# mcu_core.net
KiCad netlist of a schematic drawn in Altium Designer
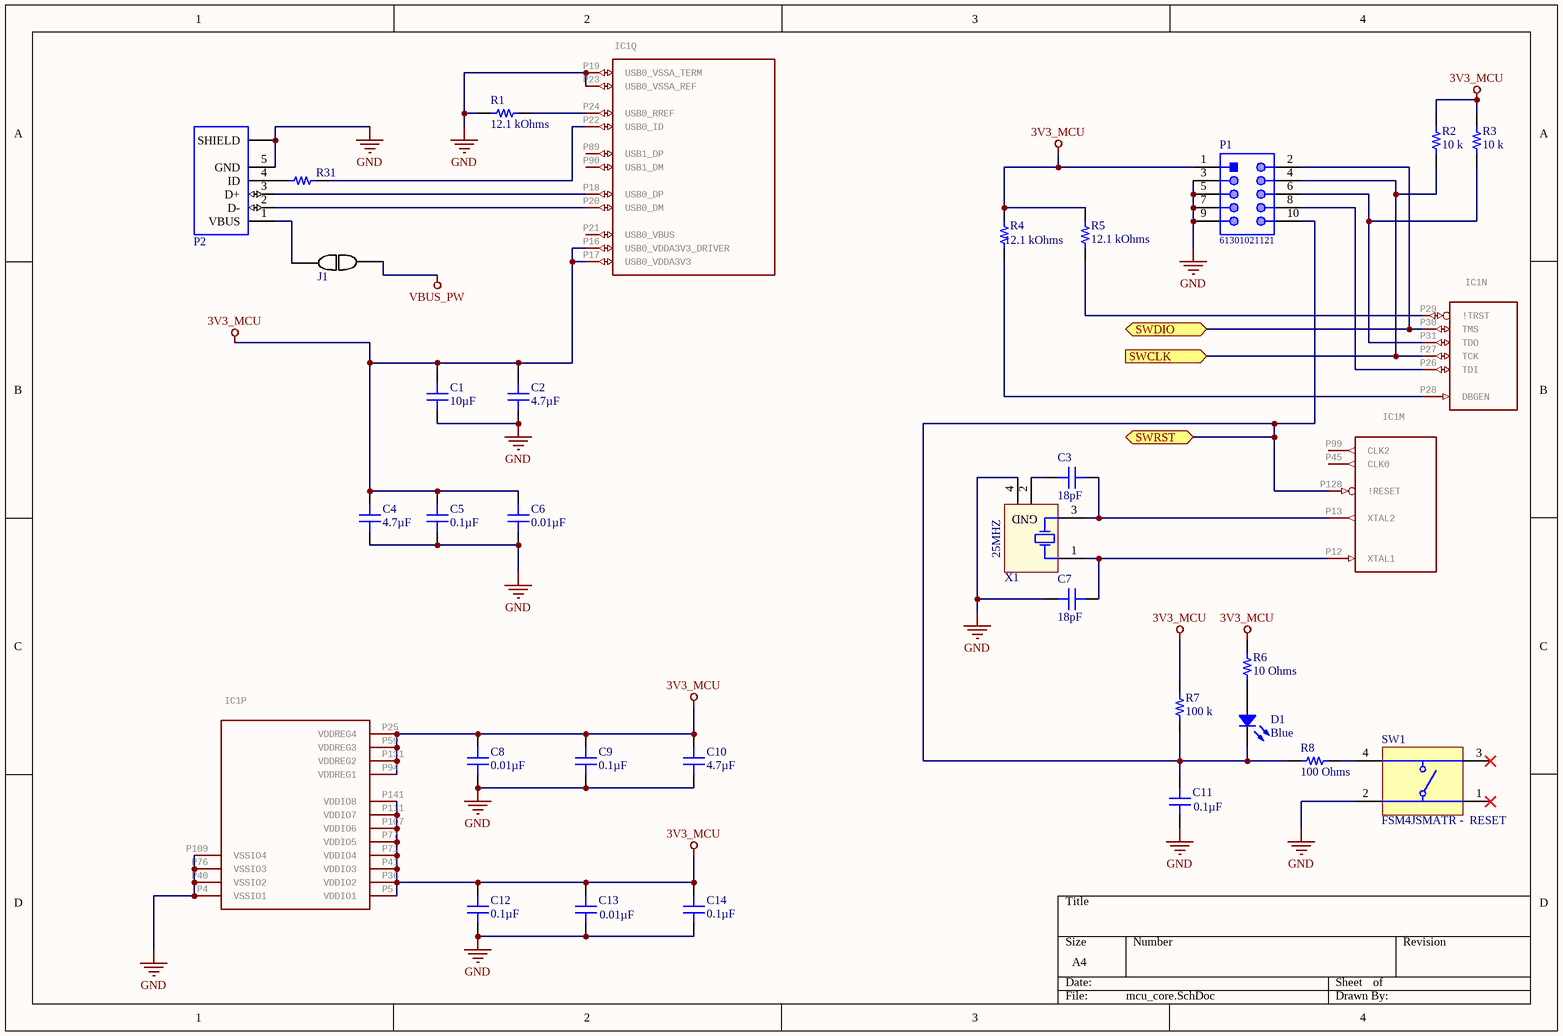
[diagram p0: mcu_core.SchDoc]

(export (version "E")
  (design (tool "Eeschema 10.0.6"))
  (components
    (comp (ref "C1")
      (value "10µF")
      (footprint "CAP 0603_1608")
      (description "CAP CER 10UF 10V X5R 0603")
      (fields
        (field (name "PART NUMBER") "GRM188R61A106MAALD")
        (field (name "MANUFACTURER") "Murata Electronics")
      )
      (libsource (lib "Celestial Altium Library - altium_library (2)") (part "Capacitor"))
    )
    (comp (ref "C2")
      (value "4.7µF")
      (footprint "CAP 0603_1608")
      (description "CAP CER 4.7UF 10V X5R 0603")
      (fields (field (name "PART NUMBER") "LMK107BJ475KA-T") (field (name "MANUFACTURER") "Taiyo Yuden"))
      (libsource (lib "Celestial Altium Library - altium_library (2)") (part "Capacitor"))
    )
    (comp (ref "C3")
      (value "18pF")
      (footprint "CAP 0603_1608")
      (description "CAP CER 18PF 10V C0G/NP0 0603")
      (fields
        (field (name "PART NUMBER") "VJ0603A180FXQCW1BC")
        (field (name "MANUFACTURER") "Vishay Vitramon")
      )
      (libsource (lib "Celestial Altium Library - altium_library (2)") (part "Capacitor"))
    )
    (comp (ref "C4")
      (value "4.7µF")
      (footprint "CAP 0603_1608")
      (description "CAP CER 4.7UF 10V X5R 0603")
      (fields (field (name "PART NUMBER") "LMK107BJ475KA-T") (field (name "MANUFACTURER") "Taiyo Yuden"))
      (libsource (lib "Celestial Altium Library - altium_library (2)") (part "Capacitor"))
    )
    (comp (ref "C5")
      (value "0.1µF")
      (footprint "CAP 0603_1608")
      (description "CAP CER 0.1UF 50V X7R 0603")
      (fields (field (name "PART NUMBER") "C0603C104K5RAC7411") (field (name "MANUFACTURER") "KEMET"))
      (libsource (lib "Celestial Altium Library - altium_library (2)") (part "Capacitor"))
    )
    (comp (ref "C6")
      (value "0.01µF")
      (footprint "CAP 0603_1608")
      (description "CAP CER 0.01UF 250V X7R 0603")
      (fields (field (name "PART NUMBER") "C0603C103KARACAUTO") (field (name "MANUFACTURER") "KEMET"))
      (libsource (lib "Celestial Altium Library - altium_library (2)") (part "Capacitor"))
    )
    (comp (ref "C7")
      (value "18pF")
      (footprint "CAP 0603_1608")
      (description "CAP CER 18PF 10V C0G/NP0 0603")
      (fields
        (field (name "PART NUMBER") "VJ0603A180FXQCW1BC")
        (field (name "MANUFACTURER") "Vishay Vitramon")
      )
      (libsource (lib "Celestial Altium Library - altium_library (2)") (part "Capacitor"))
    )
    (comp (ref "C8")
      (value "0.01µF")
      (footprint "CAP 0603_1608")
      (description "CAP CER 0.01UF 250V X7R 0603")
      (fields (field (name "PART NUMBER") "C0603C103KARACAUTO") (field (name "MANUFACTURER") "KEMET"))
      (libsource (lib "Celestial Altium Library - altium_library (2)") (part "Capacitor"))
    )
    (comp (ref "C9")
      (value "0.1µF")
      (footprint "CAP 0603_1608")
      (description "CAP CER 0.1UF 50V X7R 0603")
      (fields (field (name "PART NUMBER") "C0603C104K5RAC7411") (field (name "MANUFACTURER") "KEMET"))
      (libsource (lib "Celestial Altium Library - altium_library (2)") (part "Capacitor"))
    )
    (comp (ref "C10")
      (value "4.7µF")
      (footprint "CAP 0603_1608")
      (description "CAP CER 4.7UF 10V X5R 0603")
      (fields (field (name "PART NUMBER") "LMK107BJ475KA-T") (field (name "MANUFACTURER") "Taiyo Yuden"))
      (libsource (lib "Celestial Altium Library - altium_library (2)") (part "Capacitor"))
    )
    (comp (ref "C11")
      (value "0.1µF")
      (footprint "CAP 0603_1608")
      (description "CAP CER 0.1UF 10V X7R 0603")
      (fields (field (name "PART NUMBER") "C0603T104K8RAC7867") (field (name "MANUFACTURER") "KEMET"))
      (libsource (lib "Celestial Altium Library - altium_library (2)") (part "Capacitor"))
    )
    (comp (ref "C12")
      (value "0.1µF")
      (footprint "CAP 0603_1608")
      (description "CAP CER 0.1UF 50V X7R 0603")
      (fields (field (name "PART NUMBER") "C0603C104K5RAC7411") (field (name "MANUFACTURER") "KEMET"))
      (libsource (lib "Celestial Altium Library - altium_library (2)") (part "Capacitor"))
    )
    (comp (ref "C13")
      (value "0.01µF")
      (footprint "CAP 0603_1608")
      (description "CAP CER 0.01UF 250V X7R 0603")
      (fields (field (name "PART NUMBER") "C0603C103KARACAUTO") (field (name "MANUFACTURER") "KEMET"))
      (libsource (lib "Celestial Altium Library - altium_library (2)") (part "Capacitor"))
    )
    (comp (ref "C14")
      (value "0.1µF")
      (footprint "CAP 0603_1608")
      (description "CAP CER 0.1UF 50V X7R 0603")
      (fields (field (name "PART NUMBER") "C0603C104K5RAC7411") (field (name "MANUFACTURER") "KEMET"))
      (libsource (lib "Celestial Altium Library - altium_library (2)") (part "Capacitor"))
    )
    (comp (ref "D1")
      (value "Blue")
      (footprint "LED 0603_1608 BLUE")
      (description "LED BLUE 0603 SMD")
      (fields
        (field (name "PART NUMBER") "VLMB1300-GS08")
        (field (name "MANUFACTURER") "Vishay Semiconductor Opto Division")
      )
      (libsource (lib "Celestial Altium Library - altium_library (2)") (part "LED"))
    )
    (comp (ref "IC1")
      (value "LQFP144 - SOT486-1    LQFP144: plastic low profile quad flat package; 144 leads; body 20 x 20 x 1.4 mm    body + leads 22 x 22 mm   Solderland (pads) 0.4 x 1.5 mm on corners (8 x) and 0.28 x 1.5 mm (136 x)")
      (footprint "LQFP144")
      (libsource (lib "LPC4300") (part "LPC4300_LQFP144"))
    )
    (comp (ref "J1")
      (value "103185-2")
      (footprint "TE_103185-2")
      (description "02 MODII HDR SRST B/A .100CL")
      (libsource (lib "103185-2") (part "103185-2"))
    )
    (comp (ref "P1")
      (value "61301021121")
      (footprint "61301021121")
      (description "THT Vertical Pin Header WR-PHD, Pitch 2.54 mm, Dual Row, 10 pins")
      (fields (field (name "MANUFACTURER") "Wurth Elektronik") (field (name "PUBLISHER") "WurthElektronik"))
      (libsource (lib "Altium Content Vault") (part "WE-CN-2P-M-R10"))
    )
    (comp (ref "P2")
      (value "47346-0001")
      (footprint "MOLEX_47346-0001")
      (description "CONN RCPT 5POS MICRO USB R/A  SMD")
      (libsource (lib "47346-0001") (part "47346-0001"))
    )
    (comp (ref "R1")
      (value "12.1 kOhms")
      (footprint "RES 0603_1608")
      (description "RES SMD 12.1K OHM 1% 1/10W 0603")
      (fields (field (name "PART NUMBER") "CR0603-FX-1212ELF") (field (name "MANUFACTURER") "Bourns Inc."))
      (libsource (lib "Celestial Altium Library - altium_library (2)") (part "Resistor"))
    )
    (comp (ref "R2")
      (value "10 k")
      (footprint "RES 0603_1608")
      (description "RES 10K OHM 0.1% 1/16W 0603")
      (fields
        (field (name "PART NUMBER") "RNCS0603BKE10K0")
        (field (name "MANUFACTURER") "Stackpole Electronics Inc")
      )
      (libsource (lib "Celestial Altium Library - altium_library (2)") (part "Resistor"))
    )
    (comp (ref "R3")
      (value "10 k")
      (footprint "RES 0603_1608")
      (description "RES 10K OHM 0.1% 1/16W 0603")
      (fields
        (field (name "PART NUMBER") "RNCS0603BKE10K0")
        (field (name "MANUFACTURER") "Stackpole Electronics Inc")
      )
      (libsource (lib "Celestial Altium Library - altium_library (2)") (part "Resistor"))
    )
    (comp (ref "R4")
      (value "12.1 kOhms")
      (footprint "RES 0603_1608")
      (description "RES SMD 12.1K OHM 1% 1/10W 0603")
      (fields (field (name "PART NUMBER") "CR0603-FX-1212ELF") (field (name "MANUFACTURER") "Bourns Inc."))
      (libsource (lib "Celestial Altium Library - altium_library (2)") (part "Resistor"))
    )
    (comp (ref "R5")
      (value "12.1 kOhms")
      (footprint "RES 0603_1608")
      (description "RES SMD 12.1K OHM 1% 1/10W 0603")
      (fields (field (name "PART NUMBER") "CR0603-FX-1212ELF") (field (name "MANUFACTURER") "Bourns Inc."))
      (libsource (lib "Celestial Altium Library - altium_library (2)") (part "Resistor"))
    )
    (comp (ref "R6")
      (value "10 Ohms")
      (footprint "RES 0603_1608")
      (description "RES SMD 10 OHM 0.1% 1/10W 0603")
      (fields (field (name "PART NUMBER") "CRT0603-BY-10R0ELF") (field (name "MANUFACTURER") "Bourns Inc."))
      (libsource (lib "Celestial Altium Library - altium_library (2)") (part "Resistor"))
    )
    (comp (ref "R7")
      (value "100 k")
      (footprint "RES 0603_1608")
      (description "RES 100K OHM 5% 1/10W 0603")
      (fields
        (field (name "PART NUMBER") "RMCF0603JT100K")
        (field (name "MANUFACTURER") "Stackpole Electronics Inc")
      )
      (libsource (lib "Celestial Altium Library - altium_library (2)") (part "Resistor"))
    )
    (comp (ref "R8")
      (value "100 Ohms")
      (footprint "RES 0603_1608")
      (description "RES 100 OHM 0.1% 1/16W 0603")
      (fields
        (field (name "PART NUMBER") "RNCS0603BKE100R")
        (field (name "MANUFACTURER") "Stackpole Electronics Inc")
      )
      (libsource (lib "Celestial Altium Library - altium_library (2)") (part "Resistor"))
    )
    (comp (ref "R31")
      (value "~")
      (footprint "RES 0603_1608")
      (description "RES 0 OHM JUMPER 0603")
      (fields
        (field (name "PART NUMBER") "TLRZ1JTTD")
        (field (name "MANUFACTURER") "KOA Speer Electronics, Inc.")
      )
      (libsource (lib "Celestial Altium Library - altium_library (2)") (part "Resistor"))
    )
    (comp (ref "SW1")
      (value "FSM4JSMATR -  RESET")
      (footprint "TECO-FSM4JSMATR_V")
      (description "Micro Miniature Push Button Switch FSM JSM, 50 mA, -35 to 85 degC, 4-Pin SMD, RoHS, Tape and Reel")
      (fields (field (name "MANUFACTURER") "TE Connectivity"))
      (libsource (lib "Altium Content Vault") (part "SW-SPST-4_A"))
    )
    (comp (ref "X1")
      (value "25MHZ")
      (footprint "ABRA-ABMM2-4_V")
      (fields (field (name "MANUFACTURER") "Abracon") (field (name "PARTNUMBER") "ABMM2-8.000MHZ-E2-T"))
      (libsource (lib "Altium Content Vault") (part "ABRA-XTAL_1-3-4"))
    )
  )
  (nets
    (net (code "1") (name "/SWCLK") (class "Default")
      (node (ref "IC1") (pin "P27") (pinfunction "TCK_P27") (pintype "bidirectional"))
      (node (ref "P1") (pin "4") (pinfunction "4_4") (pintype "passive"))
      (node (ref "R2") (pin "1") (pinfunction "1_1") (pintype "passive"))
    )
    (net (code "2") (name "/SWDIO") (class "Default")
      (node (ref "IC1") (pin "P30") (pinfunction "TMS_P30") (pintype "bidirectional"))
      (node (ref "P1") (pin "2") (pinfunction "2_2") (pintype "passive"))
    )
    (net (code "3") (name "/SWRST") (class "Default")
      (node (ref "C11") (pin "1") (pinfunction "1_1") (pintype "passive"))
      (node (ref "D1") (pin "2") (pinfunction "2_2") (pintype "passive"))
      (node (ref "IC1") (pin "P128") (pinfunction "!RESET_P128") (pintype "input"))
      (node (ref "P1") (pin "10") (pinfunction "10_10") (pintype "passive"))
      (node (ref "R7") (pin "2") (pinfunction "2_2") (pintype "passive"))
      (node (ref "R8") (pin "2") (pinfunction "2_2") (pintype "passive"))
    )
    (net (code "4") (name "3V3_MCU") (class "Default")
      (node (ref "C1") (pin "2") (pinfunction "2_2") (pintype "passive"))
      (node (ref "C10") (pin "2") (pinfunction "2_2") (pintype "passive"))
      (node (ref "C12") (pin "2") (pinfunction "2_2") (pintype "passive"))
      (node (ref "C13") (pin "2") (pinfunction "2_2") (pintype "passive"))
      (node (ref "C14") (pin "2") (pinfunction "2_2") (pintype "passive"))
      (node (ref "C2") (pin "2") (pinfunction "2_2") (pintype "passive"))
      (node (ref "C4") (pin "2") (pinfunction "2_2") (pintype "passive"))
      (node (ref "C5") (pin "2") (pinfunction "2_2") (pintype "passive"))
      (node (ref "C6") (pin "2") (pinfunction "2_2") (pintype "passive"))
      (node (ref "C8") (pin "2") (pinfunction "2_2") (pintype "passive"))
      (node (ref "C9") (pin "2") (pinfunction "2_2") (pintype "passive"))
      (node (ref "IC1") (pin "P107") (pinfunction "VDDIO6_P107") (pintype "power_in"))
      (node (ref "IC1") (pin "P111") (pinfunction "VDDIO7_P111") (pintype "power_in"))
      (node (ref "IC1") (pin "P131") (pinfunction "VDDREG2_P131") (pintype "power_in"))
      (node (ref "IC1") (pin "P141") (pinfunction "VDDIO8_P141") (pintype "power_in"))
      (node (ref "IC1") (pin "P16") (pinfunction "USB0_VDDA3V3_DRIVER_P16") (pintype "bidirectional"))
      (node (ref "IC1") (pin "P17") (pinfunction "USB0_VDDA3V3_P17") (pintype "bidirectional"))
      (node (ref "IC1") (pin "P25") (pinfunction "VDDREG4_P25") (pintype "power_in"))
      (node (ref "IC1") (pin "P36") (pinfunction "VDDIO2_P36") (pintype "power_in"))
      (node (ref "IC1") (pin "P41") (pinfunction "VDDIO3_P41") (pintype "power_in"))
      (node (ref "IC1") (pin "P5") (pinfunction "VDDIO1_P5") (pintype "power_in"))
      (node (ref "IC1") (pin "P59") (pinfunction "VDDREG3_P59") (pintype "power_in"))
      (node (ref "IC1") (pin "P71") (pinfunction "VDDIO4_P71") (pintype "power_in"))
      (node (ref "IC1") (pin "P77") (pinfunction "VDDIO5_P77") (pintype "power_in"))
      (node (ref "IC1") (pin "P94") (pinfunction "VDDREG1_P94") (pintype "power_in"))
      (node (ref "P1") (pin "1") (pinfunction "1_1") (pintype "passive"))
      (node (ref "R2") (pin "2") (pinfunction "2_2") (pintype "passive"))
      (node (ref "R3") (pin "2") (pinfunction "2_2") (pintype "passive"))
      (node (ref "R4") (pin "2") (pinfunction "2_2") (pintype "passive"))
      (node (ref "R5") (pin "2") (pinfunction "2_2") (pintype "passive"))
      (node (ref "R6") (pin "2") (pinfunction "2_2") (pintype "passive"))
      (node (ref "R7") (pin "1") (pinfunction "1_1") (pintype "passive"))
    )
    (net (code "5") (name "GND") (class "Default")
      (node (ref "C1") (pin "1") (pinfunction "1_1") (pintype "passive"))
      (node (ref "C10") (pin "1") (pinfunction "1_1") (pintype "passive"))
      (node (ref "C11") (pin "2") (pinfunction "2_2") (pintype "passive"))
      (node (ref "C12") (pin "1") (pinfunction "1_1") (pintype "passive"))
      (node (ref "C13") (pin "1") (pinfunction "1_1") (pintype "passive"))
      (node (ref "C14") (pin "1") (pinfunction "1_1") (pintype "passive"))
      (node (ref "C2") (pin "1") (pinfunction "1_1") (pintype "passive"))
      (node (ref "C4") (pin "1") (pinfunction "1_1") (pintype "passive"))
      (node (ref "C5") (pin "1") (pinfunction "1_1") (pintype "passive"))
      (node (ref "C6") (pin "1") (pinfunction "1_1") (pintype "passive"))
      (node (ref "C7") (pin "1") (pinfunction "1_1") (pintype "passive"))
      (node (ref "C8") (pin "1") (pinfunction "1_1") (pintype "passive"))
      (node (ref "C9") (pin "1") (pinfunction "1_1") (pintype "passive"))
      (node (ref "IC1") (pin "P109") (pinfunction "VSSIO4_P109") (pintype "power_in"))
      (node (ref "IC1") (pin "P19") (pinfunction "USB0_VSSA_TERM_P19") (pintype "bidirectional"))
      (node (ref "IC1") (pin "P23") (pinfunction "USB0_VSSA_REF_P23") (pintype "bidirectional"))
      (node (ref "IC1") (pin "P4") (pinfunction "VSSIO1_P4") (pintype "power_in"))
      (node (ref "IC1") (pin "P40") (pinfunction "VSSIO2_P40") (pintype "power_in"))
      (node (ref "IC1") (pin "P76") (pinfunction "VSSIO3_P76") (pintype "power_in"))
      (node (ref "P1") (pin "3") (pinfunction "3_3") (pintype "passive"))
      (node (ref "P1") (pin "5") (pinfunction "5_5") (pintype "passive"))
      (node (ref "P1") (pin "7") (pinfunction "7_7") (pintype "passive"))
      (node (ref "P1") (pin "9") (pinfunction "9_9") (pintype "passive"))
      (node (ref "P2") (pin "5") (pinfunction "GND_5") (pintype "power_in"))
      (node (ref "P2") (pin "SH1") (pinfunction "SHIELD_SH1") (pintype "passive"))
      (node (ref "P2") (pin "SH2") (pinfunction "SHIELD_SH2") (pintype "passive"))
      (node (ref "P2") (pin "SH3") (pinfunction "SHIELD_SH3") (pintype "passive"))
      (node (ref "P2") (pin "SH4") (pinfunction "SHIELD_SH4") (pintype "passive"))
      (node (ref "P2") (pin "SH5") (pinfunction "SHIELD_SH5") (pintype "passive"))
      (node (ref "P2") (pin "SH6") (pinfunction "SHIELD_SH6") (pintype "passive"))
      (node (ref "R1") (pin "2") (pinfunction "2_2") (pintype "passive"))
      (node (ref "SW1") (pin "2") (pinfunction "2_2") (pintype "passive"))
      (node (ref "X1") (pin "4") (pinfunction "GND_4") (pintype "power_in"))
    )
    (net (code "6") (name "Net-(C3-Pad1)") (class "Default")
      (node (ref "C3") (pin "1") (pinfunction "1_1") (pintype "passive"))
      (node (ref "X1") (pin "2") (pinfunction "GND_2") (pintype "power_in"))
    )
    (net (code "7") (name "Net-(D1-Pad1)") (class "Default")
      (node (ref "D1") (pin "1") (pinfunction "1_1") (pintype "passive"))
      (node (ref "R6") (pin "1") (pinfunction "1_1") (pintype "passive"))
    )
    (net (code "8") (name "Net-(IC1M-XTAL1)") (class "Default")
      (node (ref "C7") (pin "2") (pinfunction "2_2") (pintype "passive"))
      (node (ref "IC1") (pin "P12") (pinfunction "XTAL1_P12") (pintype "input"))
      (node (ref "X1") (pin "1") (pinfunction "X1_1") (pintype "passive"))
    )
    (net (code "9") (name "Net-(IC1M-XTAL2)") (class "Default")
      (node (ref "C3") (pin "2") (pinfunction "2_2") (pintype "passive"))
      (node (ref "IC1") (pin "P13") (pinfunction "XTAL2_P13") (pintype "output"))
      (node (ref "X1") (pin "3") (pinfunction "X2_3") (pintype "passive"))
    )
    (net (code "10") (name "Net-(IC1N-!TRST)") (class "Default")
      (node (ref "IC1") (pin "P29") (pinfunction "!TRST_P29") (pintype "bidirectional"))
      (node (ref "R5") (pin "1") (pinfunction "1_1") (pintype "passive"))
    )
    (net (code "11") (name "Net-(IC1N-DBGEN)") (class "Default")
      (node (ref "IC1") (pin "P28") (pinfunction "DBGEN_P28") (pintype "input"))
      (node (ref "R4") (pin "1") (pinfunction "1_1") (pintype "passive"))
    )
    (net (code "12") (name "Net-(IC1N-TDI)") (class "Default")
      (node (ref "IC1") (pin "P26") (pinfunction "TDI_P26") (pintype "bidirectional"))
      (node (ref "P1") (pin "8") (pinfunction "8_8") (pintype "passive"))
    )
    (net (code "13") (name "Net-(IC1N-TDO)") (class "Default")
      (node (ref "IC1") (pin "P31") (pinfunction "TDO_P31") (pintype "bidirectional"))
      (node (ref "P1") (pin "6") (pinfunction "6_6") (pintype "passive"))
      (node (ref "R3") (pin "1") (pinfunction "1_1") (pintype "passive"))
    )
    (net (code "14") (name "Net-(IC1Q-USB0_DM)") (class "Default")
      (node (ref "IC1") (pin "P20") (pinfunction "USB0_DM_P20") (pintype "bidirectional"))
      (node (ref "P2") (pin "2") (pinfunction "D-_2") (pintype "bidirectional"))
    )
    (net (code "15") (name "Net-(IC1Q-USB0_DP)") (class "Default")
      (node (ref "IC1") (pin "P18") (pinfunction "USB0_DP_P18") (pintype "bidirectional"))
      (node (ref "P2") (pin "3") (pinfunction "D+_3") (pintype "bidirectional"))
    )
    (net (code "16") (name "Net-(IC1Q-USB0_ID)") (class "Default")
      (node (ref "IC1") (pin "P22") (pinfunction "USB0_ID_P22") (pintype "bidirectional"))
      (node (ref "R31") (pin "2") (pinfunction "2_2") (pintype "passive"))
    )
    (net (code "17") (name "Net-(IC1Q-USB0_RREF)") (class "Default")
      (node (ref "IC1") (pin "P24") (pinfunction "USB0_RREF_P24") (pintype "bidirectional"))
      (node (ref "R1") (pin "1") (pinfunction "1_1") (pintype "passive"))
    )
    (net (code "18") (name "Net-(P2-ID)") (class "Default")
      (node (ref "P2") (pin "4") (pinfunction "ID_4") (pintype "passive"))
      (node (ref "R31") (pin "1") (pinfunction "1_1") (pintype "passive"))
    )
    (net (code "19") (name "Net-(P2-VBUS)") (class "Default")
      (node (ref "J1") (pin "2") (pinfunction "2_2") (pintype "passive"))
      (node (ref "P2") (pin "1") (pinfunction "VBUS_1") (pintype "power_in"))
    )
    (net (code "20") (name "Net-(R8-Pad1)") (class "Default")
      (node (ref "R8") (pin "1") (pinfunction "1_1") (pintype "passive"))
      (node (ref "SW1") (pin "4") (pinfunction "4_4") (pintype "passive"))
    )
    (net (code "21") (name "VBUS_PW") (class "Default")
      (node (ref "J1") (pin "1") (pinfunction "1_1") (pintype "passive"))
    )
    (net (code "22") (name "unconnected-(IC1M-CLK0-PadP45)") (class "Default")
      (node (ref "IC1") (pin "P45") (pinfunction "CLK0_P45") (pintype "output"))
    )
    (net (code "23") (name "unconnected-(IC1M-CLK2-PadP99)") (class "Default")
      (node (ref "IC1") (pin "P99") (pinfunction "CLK2_P99") (pintype "output"))
    )
    (net (code "24") (name "unconnected-(IC1Q-USB0_VBUS-PadP21)") (class "Default")
      (node (ref "IC1") (pin "P21") (pinfunction "USB0_VBUS_P21") (pintype "bidirectional"))
    )
    (net (code "25") (name "unconnected-(IC1Q-USB1_DM-PadP90)") (class "Default")
      (node (ref "IC1") (pin "P90") (pinfunction "USB1_DM_P90") (pintype "bidirectional"))
    )
    (net (code "26") (name "unconnected-(IC1Q-USB1_DP-PadP89)") (class "Default")
      (node (ref "IC1") (pin "P89") (pinfunction "USB1_DP_P89") (pintype "bidirectional"))
    )
    (net (code "27") (name "unconnected-(SW1-Pad1)") (class "Default")
      (node (ref "SW1") (pin "1") (pinfunction "1_1") (pintype "passive+no_connect"))
    )
    (net (code "28") (name "unconnected-(SW1-Pad3)") (class "Default")
      (node (ref "SW1") (pin "3") (pinfunction "3_3") (pintype "passive+no_connect"))
    )
  )
)
